# ATmega328PU.net
KiCad netlist of a schematic drawn in Altium Designer
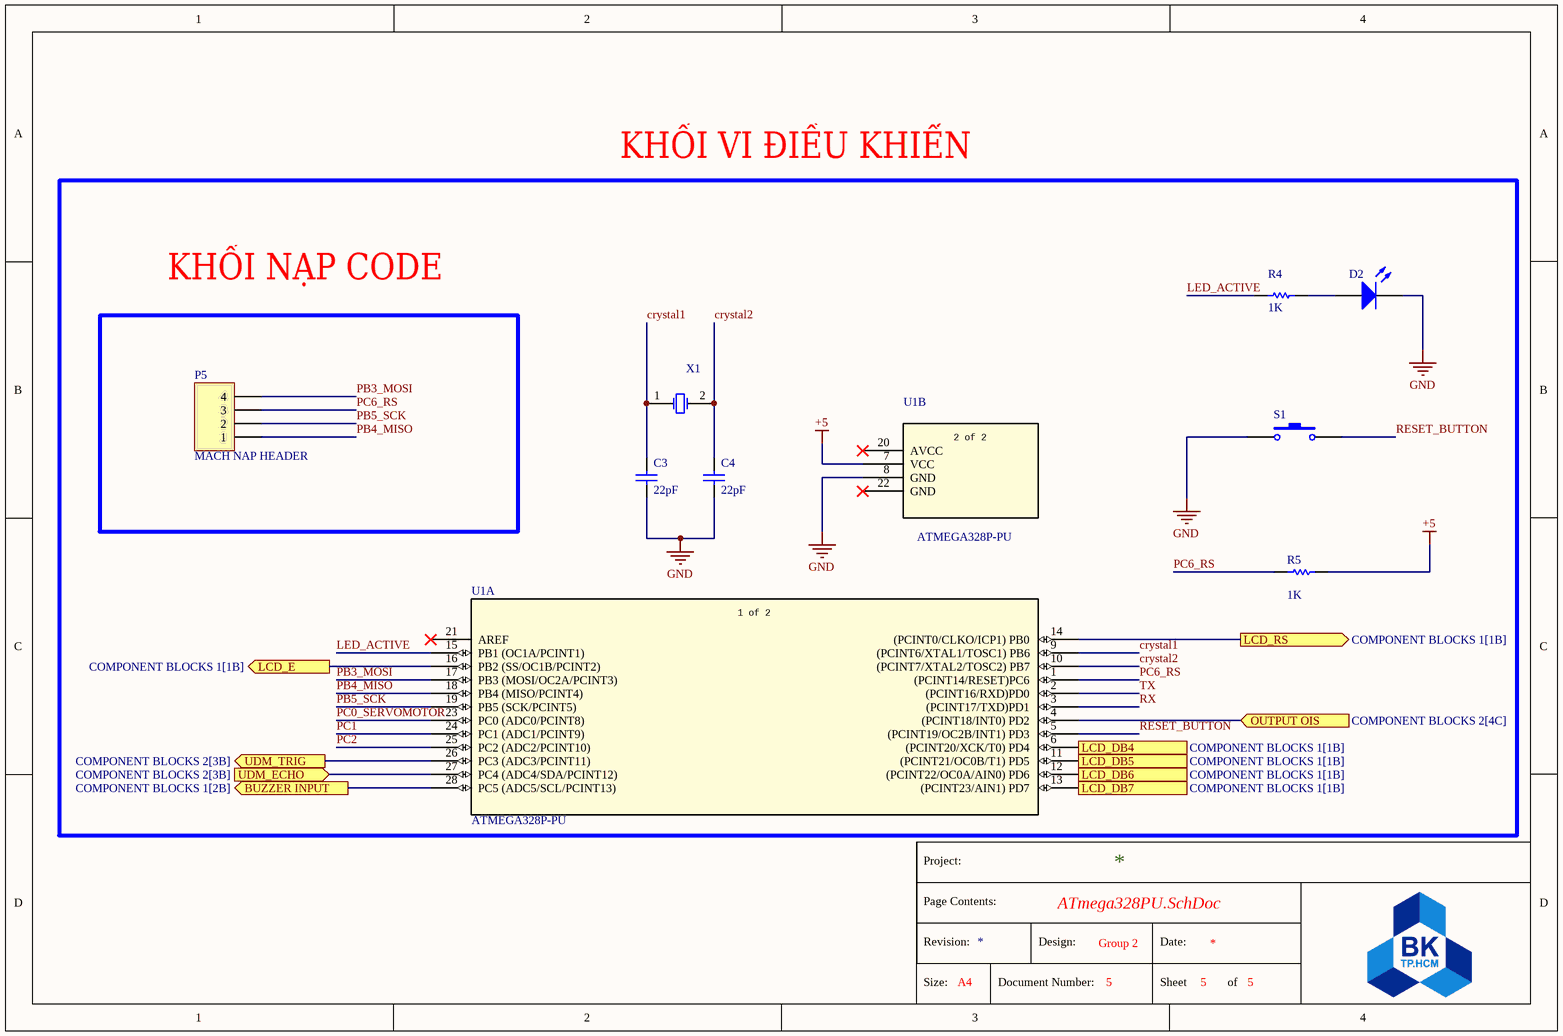
[diagram p0: ATmega328PU.SchDoc]

(export (version "E")
  (design (tool "Eeschema 10.0.6"))
  (components
    (comp (ref "C3")
      (value "22pF")
      (footprint "RAD-0.3")
      (description "Capacitor")
      (fields (field (name "Comment") "Cap") (field (name "PUBLISHER") "Altium Limited"))
      (libsource (lib "Miscellaneous Devices") (part "Cap"))
    )
    (comp (ref "C4")
      (value "22pF")
      (footprint "RAD-0.3")
      (description "Capacitor")
      (fields (field (name "Comment") "Cap") (field (name "PUBLISHER") "Altium Limited"))
      (libsource (lib "Miscellaneous Devices") (part "Cap"))
    )
    (comp (ref "D2")
      (value "LED1")
      (footprint "LED-1")
      (description "Typical RED GaAs LED")
      (fields (field (name "PUBLISHER") "Altium Limited"))
      (libsource (lib "Miscellaneous Devices") (part "LED1"))
    )
    (comp (ref "P5")
      (value "MACH NAP HEADER")
      (footprint "HDR1X4")
      (description "Header, 4-Pin")
      (fields (field (name "PUBLISHER") "Altium Limited"))
      (libsource (lib "Miscellaneous Connectors") (part "Header 4"))
    )
    (comp (ref "R4")
      (value "1K")
      (footprint "AXIAL-0.3")
      (description "Resistor")
      (fields (field (name "Comment") "Res1") (field (name "PUBLISHER") "Altium Limited"))
      (libsource (lib "Miscellaneous Devices") (part "Res1"))
    )
    (comp (ref "R5")
      (value "1K")
      (footprint "AXIAL-0.3")
      (description "Resistor")
      (fields (field (name "Comment") "Res1") (field (name "PUBLISHER") "Altium Limited"))
      (libsource (lib "Miscellaneous Devices") (part "Res1"))
    )
    (comp (ref "S1")
      (value "SW-PB")
      (footprint "SPST-2")
      (description "Switch")
      (fields (field (name "PUBLISHER") "Altium Limited"))
      (libsource (lib "Miscellaneous Devices") (part "SW-PB"))
    )
    (comp (ref "U1")
      (value "ATMEGA328P-PU")
      (footprint "28P3_ATM")
      (description "Description")
      (fields (field (name "COPYRIGHT") "Copyright (C) 2025 Ultra Librarian. All rights reserved."))
      (libsource (lib "ATMEGA328P-PU") (part "ATMEGA328P-PU"))
    )
    (comp (ref "X1")
      (value "XTAL")
      (footprint "R38")
      (description "Crystal Oscillator")
      (fields (field (name "PUBLISHER") "Altium Limited"))
      (libsource (lib "Miscellaneous Devices") (part "XTAL"))
    )
  )
  (nets
    (net (code "1") (name "+5") (class "Default")
      (node (ref "R5") (pin "2") (pinfunction "2_2") (pintype "passive"))
      (node (ref "U1") (pin "7") (pinfunction "VCC_7") (pintype "power_in"))
    )
    (net (code "2") (name "/BUZZER INPUT") (class "Default")
      (node (ref "U1") (pin "28") (pinfunction "PC5_(ADC5/SCL/PCINT13)_28") (pintype "bidirectional"))
    )
    (net (code "3") (name "/LCD_DB4") (class "Default")
      (node (ref "U1") (pin "6") (pinfunction "(PCINT20/XCK/T0)_PD4_6") (pintype "bidirectional"))
    )
    (net (code "4") (name "/LCD_DB5") (class "Default")
      (node (ref "U1") (pin "11") (pinfunction "(PCINT21/OC0B/T1)_PD5_11") (pintype "bidirectional"))
    )
    (net (code "5") (name "/LCD_DB6") (class "Default")
      (node (ref "U1") (pin "12") (pinfunction "(PCINT22/OC0A/AIN0)_PD6_12") (pintype "bidirectional"))
    )
    (net (code "6") (name "/LCD_DB7") (class "Default")
      (node (ref "U1") (pin "13") (pinfunction "(PCINT23/AIN1)_PD7_13") (pintype "bidirectional"))
    )
    (net (code "7") (name "/LCD_E") (class "Default")
      (node (ref "U1") (pin "16") (pinfunction "PB2_(SS/OC1B/PCINT2)_16") (pintype "bidirectional"))
    )
    (net (code "8") (name "/LCD_RS") (class "Default")
      (node (ref "U1") (pin "14") (pinfunction "(PCINT0/CLKO/ICP1)_PB0_14") (pintype "bidirectional"))
    )
    (net (code "9") (name "/LED_ACTIVE") (class "Default")
      (node (ref "R4") (pin "1") (pinfunction "1_1") (pintype "passive"))
      (node (ref "U1") (pin "15") (pinfunction "PB1_(OC1A/PCINT1)_15") (pintype "bidirectional"))
    )
    (net (code "10") (name "/OUTPUT OIS") (class "Default")
      (node (ref "U1") (pin "4") (pinfunction "(PCINT18/INT0)_PD2_4") (pintype "bidirectional"))
    )
    (net (code "11") (name "/PB3_MOSI") (class "Default")
      (node (ref "P5") (pin "4") (pinfunction "4_4") (pintype "passive"))
      (node (ref "U1") (pin "17") (pinfunction "PB3_(MOSI/OC2A/PCINT3)_17") (pintype "bidirectional"))
    )
    (net (code "12") (name "/PB4_MISO") (class "Default")
      (node (ref "P5") (pin "1") (pinfunction "1_1") (pintype "passive"))
      (node (ref "U1") (pin "18") (pinfunction "PB4_(MISO/PCINT4)_18") (pintype "bidirectional"))
    )
    (net (code "13") (name "/PB5_SCK") (class "Default")
      (node (ref "P5") (pin "2") (pinfunction "2_2") (pintype "passive"))
      (node (ref "U1") (pin "19") (pinfunction "PB5_(SCK/PCINT5)_19") (pintype "bidirectional"))
    )
    (net (code "14") (name "/PC0_SERVOMOTOR") (class "Default")
      (node (ref "U1") (pin "23") (pinfunction "PC0_(ADC0/PCINT8)_23") (pintype "bidirectional"))
    )
    (net (code "15") (name "/PC1") (class "Default")
      (node (ref "U1") (pin "24") (pinfunction "PC1_(ADC1/PCINT9)_24") (pintype "bidirectional"))
    )
    (net (code "16") (name "/PC2") (class "Default")
      (node (ref "U1") (pin "25") (pinfunction "PC2_(ADC2/PCINT10)_25") (pintype "bidirectional"))
    )
    (net (code "17") (name "/PC6_RS") (class "Default")
      (node (ref "P5") (pin "3") (pinfunction "3_3") (pintype "passive"))
      (node (ref "R5") (pin "1") (pinfunction "1_1") (pintype "passive"))
      (node (ref "U1") (pin "1") (pinfunction "(PCINT14/RESET)PC6_1") (pintype "bidirectional"))
    )
    (net (code "18") (name "/RESET_BUTTON") (class "Default")
      (node (ref "S1") (pin "2") (pinfunction "2_2") (pintype "passive"))
      (node (ref "U1") (pin "5") (pinfunction "(PCINT19/OC2B/INT1)_PD3_5") (pintype "bidirectional"))
    )
    (net (code "19") (name "/RX") (class "Default")
      (node (ref "U1") (pin "3") (pinfunction "(PCINT17/TXD)PD1_3") (pintype "bidirectional"))
    )
    (net (code "20") (name "/TX") (class "Default")
      (node (ref "U1") (pin "2") (pinfunction "(PCINT16/RXD)PD0_2") (pintype "bidirectional"))
    )
    (net (code "21") (name "/UDM_ECHO") (class "Default")
      (node (ref "U1") (pin "27") (pinfunction "PC4_(ADC4/SDA/PCINT12)_27") (pintype "bidirectional"))
    )
    (net (code "22") (name "/UDM_TRIG") (class "Default")
      (node (ref "U1") (pin "26") (pinfunction "PC3_(ADC3/PCINT11)_26") (pintype "bidirectional"))
    )
    (net (code "23") (name "/crystal1") (class "Default")
      (node (ref "C3") (pin "2") (pinfunction "2_2") (pintype "passive"))
      (node (ref "U1") (pin "9") (pinfunction "(PCINT6/XTAL1/TOSC1)_PB6_9") (pintype "bidirectional"))
      (node (ref "X1") (pin "1") (pinfunction "OSC1_1") (pintype "passive"))
    )
    (net (code "24") (name "/crystal2") (class "Default")
      (node (ref "C4") (pin "2") (pinfunction "2_2") (pintype "passive"))
      (node (ref "U1") (pin "10") (pinfunction "(PCINT7/XTAL2/TOSC2)_PB7_10") (pintype "bidirectional"))
      (node (ref "X1") (pin "2") (pinfunction "OSC2_2") (pintype "passive"))
    )
    (net (code "25") (name "GND") (class "Default")
      (node (ref "C3") (pin "1") (pinfunction "1_1") (pintype "passive"))
      (node (ref "C4") (pin "1") (pinfunction "1_1") (pintype "passive"))
      (node (ref "D2") (pin "2") (pinfunction "K_2") (pintype "passive"))
      (node (ref "S1") (pin "1") (pinfunction "1_1") (pintype "passive"))
      (node (ref "U1") (pin "8") (pinfunction "GND_8") (pintype "power_in"))
    )
    (net (code "26") (name "Net-(D2-A)") (class "Default")
      (node (ref "D2") (pin "1") (pinfunction "A_1") (pintype "passive"))
      (node (ref "R4") (pin "2") (pinfunction "2_2") (pintype "passive"))
    )
    (net (code "27") (name "unconnected-(U1A-AREF-Pad21)") (class "Default")
      (node (ref "U1") (pin "21") (pinfunction "AREF_21") (pintype "passive+no_connect"))
    )
    (net (code "28") (name "unconnected-(U1B-AVCC-Pad20)") (class "Default")
      (node (ref "U1") (pin "20") (pinfunction "AVCC_20") (pintype "power_in+no_connect"))
    )
    (net (code "29") (name "unconnected-(U1B-GND-Pad22)") (class "Default")
      (node (ref "U1") (pin "22") (pinfunction "GND_22") (pintype "power_in+no_connect"))
    )
  )
)
